# Sheet1.net
KiCad netlist of a schematic drawn in Altium Designer
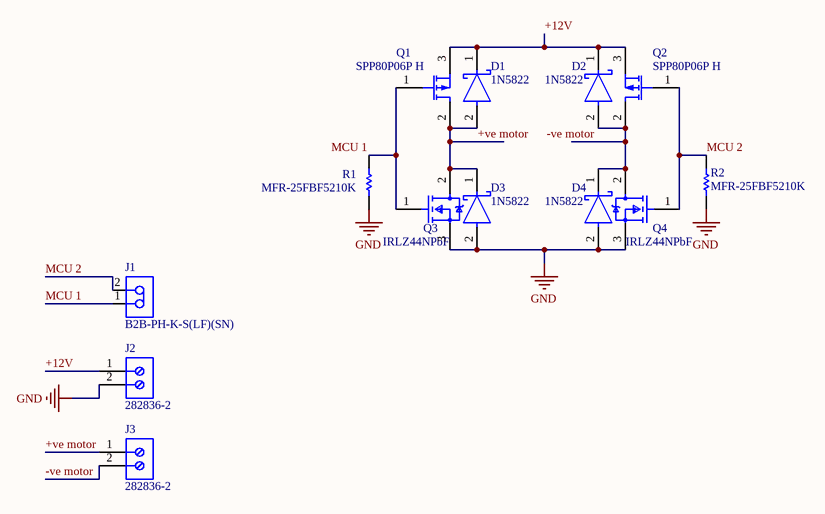
[diagram p0: Sheet1.SchDoc]

(export (version "E")
  (design (tool "Eeschema 10.0.6"))
  (components
    (comp (ref "D1")
      (value "1N5822")
      (footprint "FP-DO-201AD-MFG")
      (description "DIODE SCHOTTKY 40V 3A DO201AD")
      (fields
        (field (name "OCTOPART") "https://octopart.com/1n5822-stmicroelectronics-323225")
        (field (name "MANUFACTURER") "STMicroelectronics")
      )
      (libsource (lib "Altium Content Vault") (part "1d6ec82d83fb6aee721767c19dac4b9"))
    )
    (comp (ref "D2")
      (value "1N5822")
      (footprint "FP-DO-201AD-MFG")
      (description "DIODE SCHOTTKY 40V 3A DO201AD")
      (fields
        (field (name "OCTOPART") "https://octopart.com/1n5822-stmicroelectronics-323225")
        (field (name "MANUFACTURER") "STMicroelectronics")
      )
      (libsource (lib "Altium Content Vault") (part "1d6ec82d83fb6aee721767c19dac4b9"))
    )
    (comp (ref "D3")
      (value "1N5822")
      (footprint "FP-DO-201AD-MFG")
      (description "DIODE SCHOTTKY 40V 3A DO201AD")
      (fields
        (field (name "OCTOPART") "https://octopart.com/1n5822-stmicroelectronics-323225")
        (field (name "MANUFACTURER") "STMicroelectronics")
      )
      (libsource (lib "Altium Content Vault") (part "1d6ec82d83fb6aee721767c19dac4b9"))
    )
    (comp (ref "D4")
      (value "1N5822")
      (footprint "FP-DO-201AD-MFG")
      (description "DIODE SCHOTTKY 40V 3A DO201AD")
      (fields
        (field (name "OCTOPART") "https://octopart.com/1n5822-stmicroelectronics-323225")
        (field (name "MANUFACTURER") "STMicroelectronics")
      )
      (libsource (lib "Altium Content Vault") (part "1d6ec82d83fb6aee721767c19dac4b9"))
    )
    (comp (ref "J1")
      (value "B2B-PH-K-S(LF)(SN)")
      (footprint "JST-B2B-PH-K-S_V")
      (fields (field (name "MANUFACTURER") "JST"))
      (libsource (lib "Altium Content Vault") (part "CN-2P-F-QF2"))
    )
    (comp (ref "J2")
      (value "282836-2")
      (footprint "TECO-282836-2_V")
      (description "Female Header, Pitch 5 mm, 1 x 2 Position, Height 10 mm, Tail Length 3.5 mm, Rohs, Bulk")
      (fields (field (name "VOLTAGE") "300V") (field (name "MANUFACTURER") "TE Connectivity"))
      (libsource (lib "Altium Content Vault") (part "CN-1P-F-TB2"))
    )
    (comp (ref "J3")
      (value "282836-2")
      (footprint "TECO-282836-2_V")
      (description "Female Header, Pitch 5 mm, 1 x 2 Position, Height 10 mm, Tail Length 3.5 mm, Rohs, Bulk")
      (fields (field (name "VOLTAGE") "300V") (field (name "MANUFACTURER") "TE Connectivity"))
      (libsource (lib "Altium Content Vault") (part "CN-1P-F-TB2"))
    )
    (comp (ref "Q1")
      (value "SPP80P06P H")
      (footprint "INF-PG-TO220-3-1_A_V")
      (description "P-Channel SIPMOS Power-Transistor, -60 V VDS, -80 A ID, -55 to 175 degC, PG-TO220-3-1, Tube, Green")
      (fields (field (name "MANUFACTURER") "Infineon"))
      (libsource (lib "Altium Content Vault") (part "INF-SPP80P06PH-PG-TO220-3-1_A-3"))
    )
    (comp (ref "Q2")
      (value "SPP80P06P H")
      (footprint "INF-PG-TO220-3-1_A_V")
      (description "P-Channel SIPMOS Power-Transistor, -60 V VDS, -80 A ID, -55 to 175 degC, PG-TO220-3-1, Tube, Green")
      (fields (field (name "MANUFACTURER") "Infineon"))
      (libsource (lib "Altium Content Vault") (part "INF-SPP80P06PH-PG-TO220-3-1_A-3"))
    )
    (comp (ref "Q3")
      (value "IRLZ44NPbF")
      (footprint "FP-PG-TO220-3-MFG")
      (description "MOSFET N-CH 55V 47A TO220AB")
      (libsource (lib "Altium Content Vault") (part "b09f7f152735e370c1ea22a33fa83d6"))
    )
    (comp (ref "Q4")
      (value "IRLZ44NPbF")
      (footprint "FP-PG-TO220-3-MFG")
      (description "MOSFET N-CH 55V 47A TO220AB")
      (libsource (lib "Altium Content Vault") (part "b09f7f152735e370c1ea22a33fa83d6"))
    )
    (comp (ref "R1")
      (value "MFR-25FBF5210K")
      (footprint "RESA60-630X240")
      (description "Axial Resistor, 10 KOhm, +/- 1%, 0.25 W, -55 to 155 degC, 2-Pin THD, RoHS, Bulk")
      (fields (field (name "TOLERANCE") "1%") (field (name "MANUFACTURER") "Yageo"))
      (libsource (lib "Altium Content Vault") (part "RES-2"))
    )
    (comp (ref "R2")
      (value "MFR-25FBF5210K")
      (footprint "RESA60-630X240")
      (description "Axial Resistor, 10 KOhm, +/- 1%, 0.25 W, -55 to 155 degC, 2-Pin THD, RoHS, Bulk")
      (fields (field (name "TOLERANCE") "1%") (field (name "MANUFACTURER") "Yageo"))
      (libsource (lib "Altium Content Vault") (part "RES-2"))
    )
  )
  (nets
    (net (code "1") (name "/+12V") (class "Default")
      (node (ref "D1") (pin "1") (pinfunction "C_1") (pintype "passive"))
      (node (ref "D2") (pin "1") (pinfunction "C_1") (pintype "passive"))
      (node (ref "J2") (pin "1") (pinfunction "1_1") (pintype "passive"))
      (node (ref "Q1") (pin "3") (pinfunction "S_3") (pintype "passive"))
      (node (ref "Q2") (pin "3") (pinfunction "S_3") (pintype "passive"))
    )
    (net (code "2") (name "/+ve motor") (class "Default")
      (node (ref "D1") (pin "2") (pinfunction "A_2") (pintype "passive"))
      (node (ref "D3") (pin "1") (pinfunction "C_1") (pintype "passive"))
      (node (ref "J3") (pin "1") (pinfunction "1_1") (pintype "passive"))
      (node (ref "Q1") (pin "2") (pinfunction "D_2") (pintype "passive"))
      (node (ref "Q3") (pin "2") (pinfunction "D_2") (pintype "passive"))
    )
    (net (code "3") (name "/-ve motor") (class "Default")
      (node (ref "D2") (pin "2") (pinfunction "A_2") (pintype "passive"))
      (node (ref "D4") (pin "1") (pinfunction "C_1") (pintype "passive"))
      (node (ref "J3") (pin "2") (pinfunction "2_2") (pintype "passive"))
      (node (ref "Q2") (pin "2") (pinfunction "D_2") (pintype "passive"))
      (node (ref "Q4") (pin "2") (pinfunction "D_2") (pintype "passive"))
    )
    (net (code "4") (name "/MCU 1") (class "Default")
      (node (ref "J1") (pin "1") (pinfunction "1_1") (pintype "passive"))
      (node (ref "Q1") (pin "1") (pinfunction "G_1") (pintype "passive"))
      (node (ref "Q3") (pin "1") (pinfunction "G_1") (pintype "passive"))
      (node (ref "R1") (pin "2") (pinfunction "2_2") (pintype "passive"))
    )
    (net (code "5") (name "/MCU 2") (class "Default")
      (node (ref "J1") (pin "2") (pinfunction "2_2") (pintype "passive"))
      (node (ref "Q2") (pin "1") (pinfunction "G_1") (pintype "passive"))
      (node (ref "Q4") (pin "1") (pinfunction "G_1") (pintype "passive"))
      (node (ref "R2") (pin "2") (pinfunction "2_2") (pintype "passive"))
    )
    (net (code "6") (name "GND") (class "Default")
      (node (ref "D3") (pin "2") (pinfunction "A_2") (pintype "passive"))
      (node (ref "D4") (pin "2") (pinfunction "A_2") (pintype "passive"))
      (node (ref "J2") (pin "2") (pinfunction "2_2") (pintype "passive"))
      (node (ref "Q3") (pin "3") (pinfunction "S_3") (pintype "passive"))
      (node (ref "Q4") (pin "3") (pinfunction "S_3") (pintype "passive"))
      (node (ref "R1") (pin "1") (pinfunction "1_1") (pintype "passive"))
      (node (ref "R2") (pin "1") (pinfunction "1_1") (pintype "passive"))
    )
  )
)
